# 05_-Power.net
KiCad netlist of a schematic drawn in Altium Designer
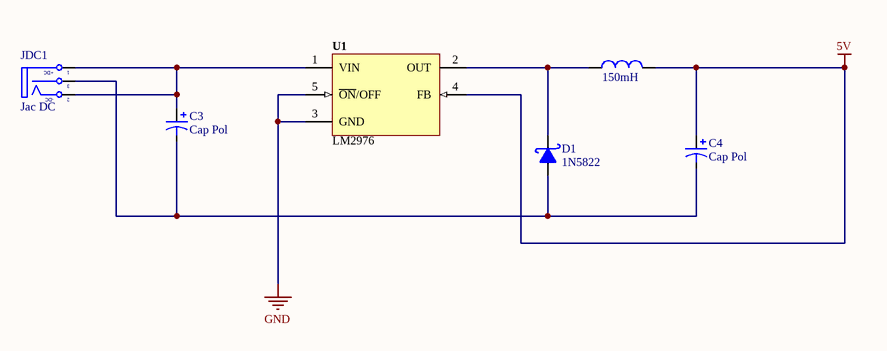
[diagram p0: [05]-Power.SchDoc]

(export (version "E")
  (design (tool "Eeschema 10.0.6"))
  (components
    (comp (ref "C3")
      (value "Cap Pol")
      (footprint "C10mm")
      (description "Polarized Capacitor (Axial)")
      (fields (field (name "PUBLISHER") "Altium Limited"))
      (libsource (lib "My Library") (part "Cap Pol"))
    )
    (comp (ref "C4")
      (value "Cap Pol")
      (footprint "C10mm")
      (description "Polarized Capacitor (Axial)")
      (fields (field (name "PUBLISHER") "Altium Limited"))
      (libsource (lib "My Library") (part "Cap Pol"))
    )
    (comp (ref "D1")
      (value "1N5822")
      (footprint "SMA")
      (description "Schottky Rectifiers")
      (libsource (lib "My Library") (part "1N5822"))
    )
    (comp (ref "JDC1")
      (value "Jac DC")
      (footprint "DC-IN")
      (description "Jac DC input")
      (libsource (lib "My Library") (part "DCIN"))
    )
    (comp (ref "L2")
      (value "150mH")
      (footprint "L-SMD-M-7.3x4.5")
      (description "Inductor")
      (libsource (lib "My Library") (part "Inductor"))
    )
    (comp (ref "U1") (value "LM2976") (footprint "TO-263") (libsource (lib "My Library") (part "LM2596")))
  )
  (nets
    (net (code "1") (name "5V") (class "Default")
      (node (ref "C4") (pin "1") (pinfunction "1_1") (pintype "passive"))
      (node (ref "L2") (pin "2") (pinfunction "2_2") (pintype "passive"))
      (node (ref "U1") (pin "4") (pinfunction "FB_4") (pintype "input"))
    )
    (net (code "2") (name "GND") (class "Default")
      (node (ref "U1") (pin "3") (pinfunction "GND_3") (pintype "power_in"))
      (node (ref "U1") (pin "5") (pinfunction "~{ON}/OFF_5") (pintype "input"))
    )
    (net (code "3") (name "Net-(D1-A)") (class "Default")
      (node (ref "C3") (pin "2") (pinfunction "2_2") (pintype "passive"))
      (node (ref "C4") (pin "2") (pinfunction "2_2") (pintype "passive"))
      (node (ref "D1") (pin "1") (pinfunction "A_1") (pintype "passive"))
      (node (ref "JDC1") (pin "3") (pinfunction "S_3") (pintype "power_in"))
    )
    (net (code "4") (name "Net-(D1-K)") (class "Default")
      (node (ref "D1") (pin "2") (pinfunction "K_2") (pintype "passive"))
      (node (ref "L2") (pin "1") (pinfunction "1_1") (pintype "passive"))
      (node (ref "U1") (pin "2") (pinfunction "OUT_2") (pintype "power_in"))
    )
    (net (code "5") (name "Net-(JDC1-T)") (class "Default")
      (node (ref "C3") (pin "1") (pinfunction "1_1") (pintype "passive"))
      (node (ref "JDC1") (pin "1") (pinfunction "T_1") (pintype "passive"))
      (node (ref "JDC1") (pin "2") (pinfunction "TN_2") (pintype "passive"))
      (node (ref "U1") (pin "1") (pinfunction "VIN_1") (pintype "power_in"))
    )
  )
)
